# INC-QT1-R-005.net
KiCad netlist of a schematic drawn in Altium Designer
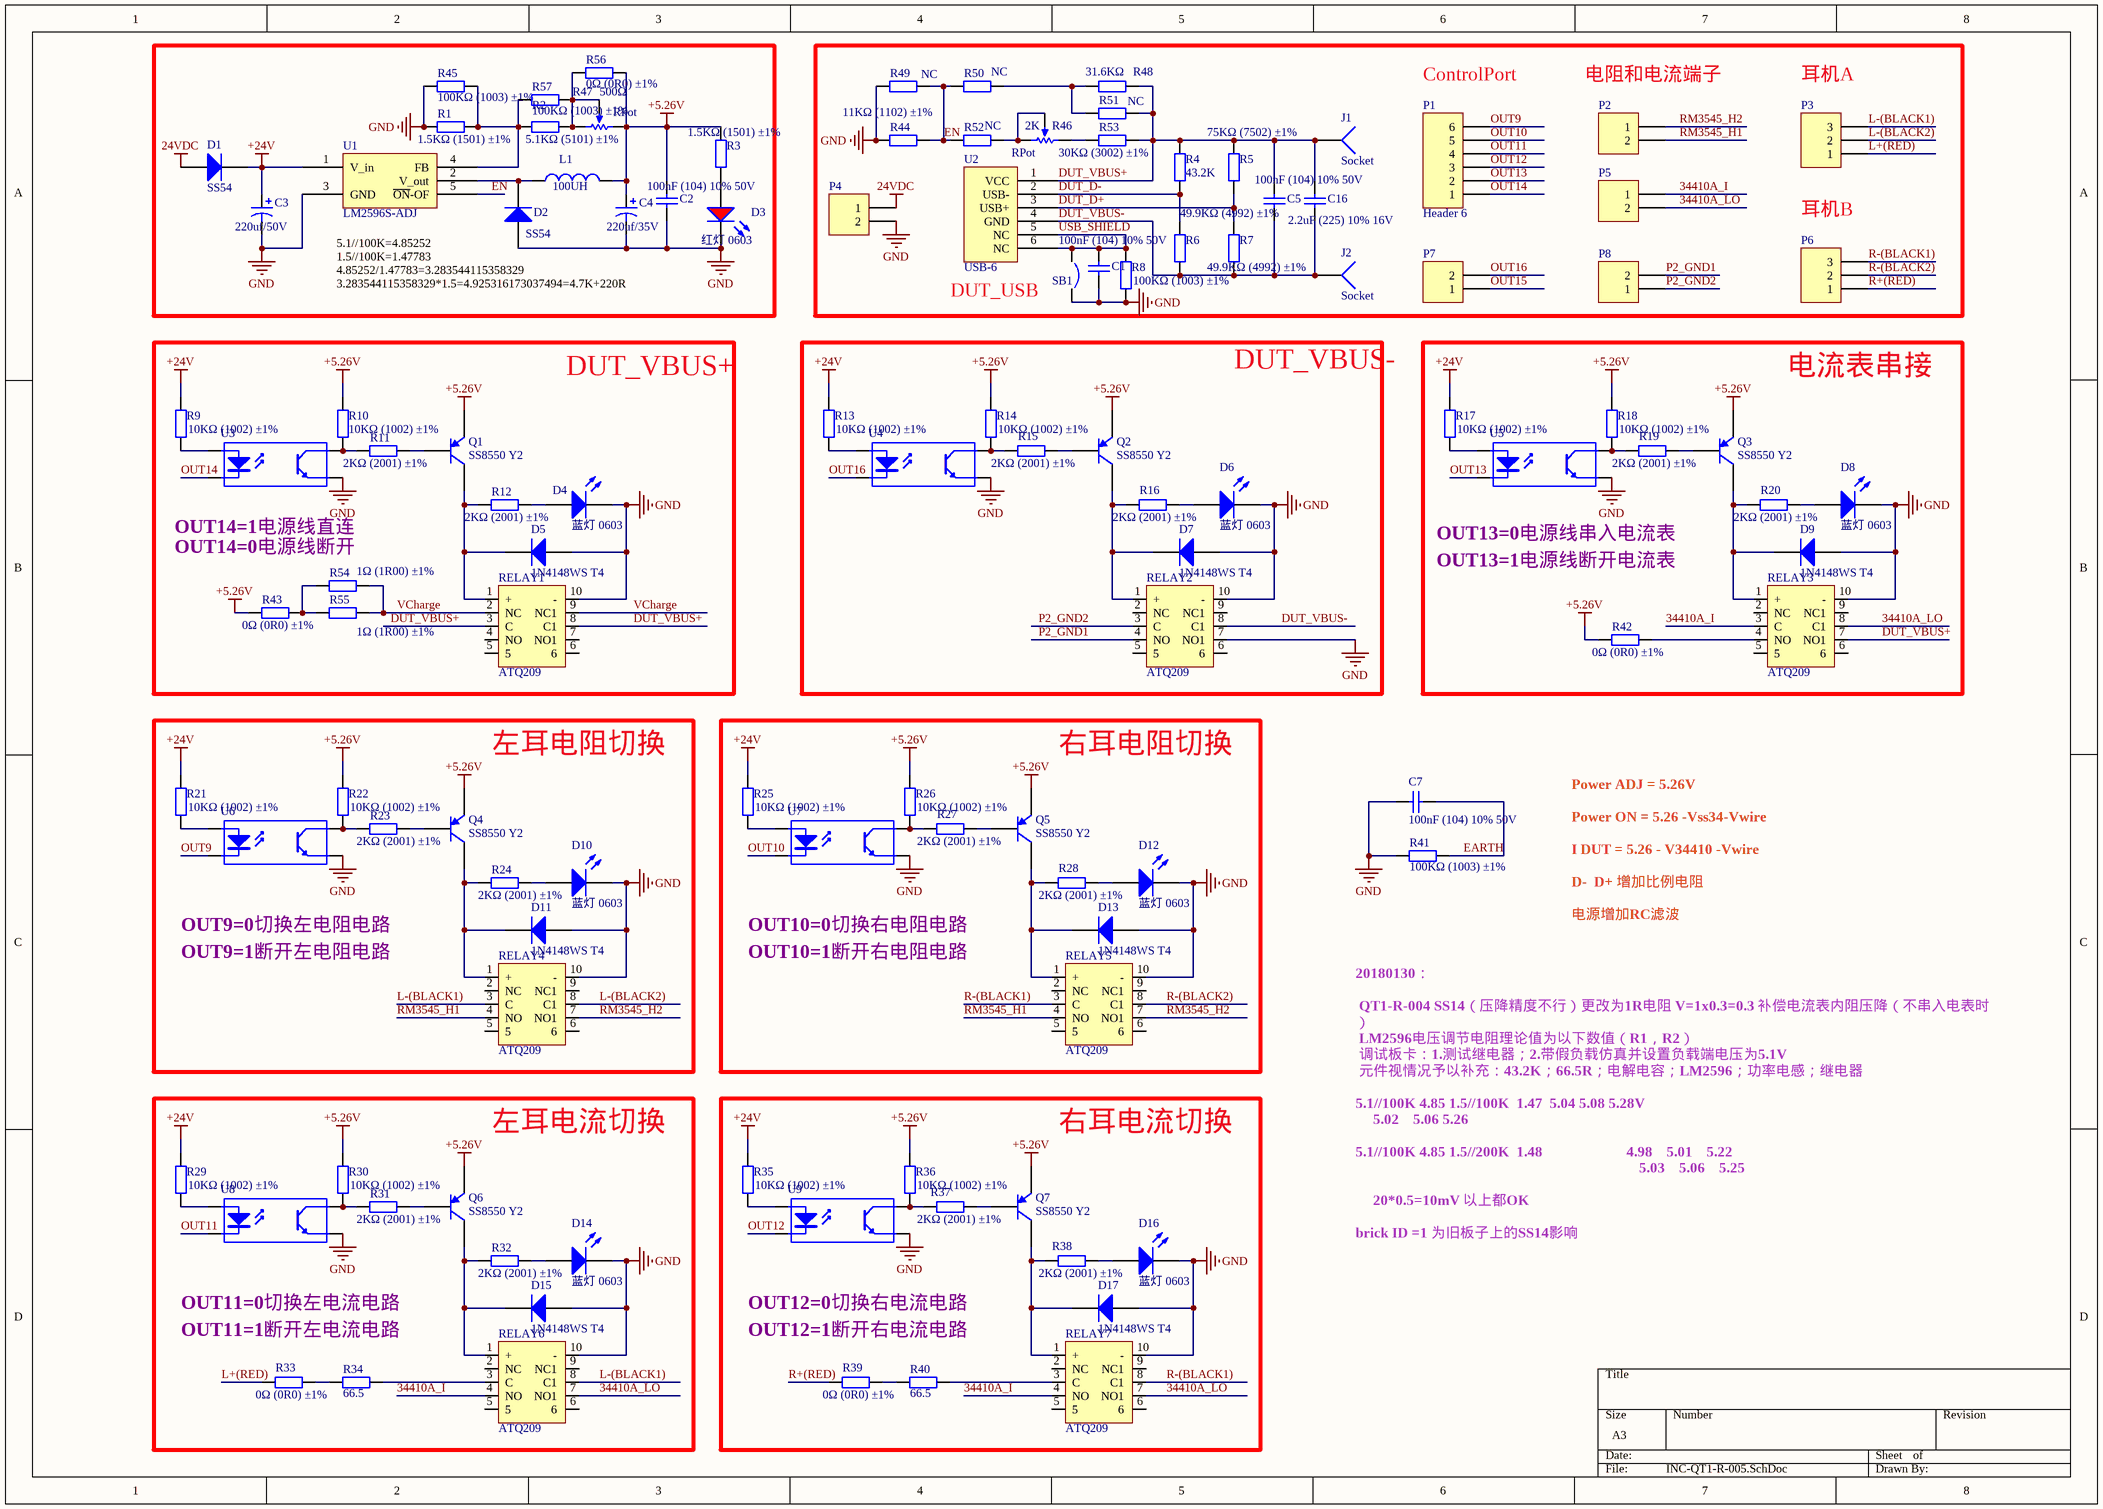
[diagram p0: INC-QT1-R-005.SchDoc]

(export (version "E")
  (design (tool "Eeschema 10.0.6"))
  (components
    (comp (ref "C1")
      (value "100nF (104) 10% 50V")
      (footprint "0603_C")
      (description "贴片电容")
      (libsource (lib "Miscellaneous Devices LC") (part "0603 100nF (104) 10% 50V"))
    )
    (comp (ref "C2")
      (value "100nF (104) 10% 50V")
      (footprint "0603_C")
      (description "贴片电容")
      (libsource (lib "Miscellaneous Devices LC") (part "0603 100nF (104) 10% 50V"))
    )
    (comp (ref "C3")
      (value "220uf/50V")
      (footprint "贴片电解 10mm X 10mm")
      (description "Polarized Capacitor (Radial)")
      (fields (field (name "PUBLISHER") "Altium Limited"))
      (libsource (lib "Miscellaneous Devices") (part "Cap Pol1"))
    )
    (comp (ref "C4")
      (value "220uf/35V")
      (footprint "贴片电解 8mm X 10mm")
      (description "Polarized Capacitor (Radial)")
      (fields (field (name "PUBLISHER") "Altium Limited"))
      (libsource (lib "Miscellaneous Devices") (part "Cap Pol1"))
    )
    (comp (ref "C5")
      (value "100nF (104) 10% 50V")
      (footprint "0603_C")
      (description "贴片电容")
      (libsource (lib "Miscellaneous Devices LC") (part "0603 100nF (104) 10% 50V"))
    )
    (comp (ref "C7")
      (value "100nF (104) 10% 50V")
      (footprint "0603_C")
      (description "贴片电容")
      (libsource (lib "Miscellaneous Devices LC") (part "0603 100nF (104) 10% 50V"))
    )
    (comp (ref "C16")
      (value "2.2uF (225) 10% 16V")
      (footprint "0603_C")
      (description "贴片电容")
      (libsource (lib "Miscellaneous Devices LC") (part "0603 2.2uF (225) 10% 16V"))
    )
    (comp (ref "D1")
      (value "SS54")
      (footprint "SMA(DO-214AC)_S1")
      (description "二极管")
      (libsource (lib "Miscellaneous Devices LC") (part "SMA(DO-214AC) SS54"))
    )
    (comp (ref "D2")
      (value "SS54")
      (footprint "SMA(DO-214AC)_S1")
      (description "二极管")
      (libsource (lib "Miscellaneous Devices LC") (part "SMA(DO-214AC) SS54"))
    )
    (comp (ref "D3")
      (value "红灯 0603")
      (footprint "0603_LED_S1")
      (description "发光二极管")
      (libsource (lib "Miscellaneous Devices LC") (part "0603 红灯"))
    )
    (comp (ref "D4")
      (value "蓝灯 0603")
      (footprint "0603_LED_S1")
      (description "发光二极管")
      (libsource (lib "Miscellaneous Devices LC") (part "0603 蓝灯"))
    )
    (comp (ref "D5")
      (value "1N4148WS T4")
      (footprint "SOD-323")
      (description "二极管")
      (libsource (lib "Miscellaneous Devices LC") (part "SOD-323 1N4148WS T4"))
    )
    (comp (ref "D6")
      (value "蓝灯 0603")
      (footprint "0603_LED_S1")
      (description "发光二极管")
      (libsource (lib "Miscellaneous Devices LC") (part "0603 蓝灯"))
    )
    (comp (ref "D7")
      (value "1N4148WS T4")
      (footprint "SOD-323")
      (description "二极管")
      (libsource (lib "Miscellaneous Devices LC") (part "SOD-323 1N4148WS T4"))
    )
    (comp (ref "D8")
      (value "蓝灯 0603")
      (footprint "0603_LED_S1")
      (description "发光二极管")
      (libsource (lib "Miscellaneous Devices LC") (part "0603 蓝灯"))
    )
    (comp (ref "D9")
      (value "1N4148WS T4")
      (footprint "SOD-323")
      (description "二极管")
      (libsource (lib "Miscellaneous Devices LC") (part "SOD-323 1N4148WS T4"))
    )
    (comp (ref "D10")
      (value "蓝灯 0603")
      (footprint "0603_LED_S1")
      (description "发光二极管")
      (libsource (lib "Miscellaneous Devices LC") (part "0603 蓝灯"))
    )
    (comp (ref "D11")
      (value "1N4148WS T4")
      (footprint "SOD-323")
      (description "二极管")
      (libsource (lib "Miscellaneous Devices LC") (part "SOD-323 1N4148WS T4"))
    )
    (comp (ref "D12")
      (value "蓝灯 0603")
      (footprint "0603_LED_S1")
      (description "发光二极管")
      (libsource (lib "Miscellaneous Devices LC") (part "0603 蓝灯"))
    )
    (comp (ref "D13")
      (value "1N4148WS T4")
      (footprint "SOD-323")
      (description "二极管")
      (libsource (lib "Miscellaneous Devices LC") (part "SOD-323 1N4148WS T4"))
    )
    (comp (ref "D14")
      (value "蓝灯 0603")
      (footprint "0603_LED_S1")
      (description "发光二极管")
      (libsource (lib "Miscellaneous Devices LC") (part "0603 蓝灯"))
    )
    (comp (ref "D15")
      (value "1N4148WS T4")
      (footprint "SOD-323")
      (description "二极管")
      (libsource (lib "Miscellaneous Devices LC") (part "SOD-323 1N4148WS T4"))
    )
    (comp (ref "D16")
      (value "蓝灯 0603")
      (footprint "0603_LED_S1")
      (description "发光二极管")
      (libsource (lib "Miscellaneous Devices LC") (part "0603 蓝灯"))
    )
    (comp (ref "D17")
      (value "1N4148WS T4")
      (footprint "SOD-323")
      (description "二极管")
      (libsource (lib "Miscellaneous Devices LC") (part "SOD-323 1N4148WS T4"))
    )
    (comp (ref "J1")
      (value "Socket")
      (footprint "TP")
      (fields (field (name "PUBLISHER") "Altium Limited"))
      (libsource (lib "Miscellaneous Connectors") (part "Socket"))
    )
    (comp (ref "J2")
      (value "Socket")
      (footprint "TP")
      (fields (field (name "PUBLISHER") "Altium Limited"))
      (libsource (lib "Miscellaneous Connectors") (part "Socket"))
    )
    (comp (ref "L1")
      (value "100UH")
      (footprint "贴片电感 12*12")
      (description "Inductor")
      (fields (field (name "PUBLISHER") "Altium Limited"))
      (libsource (lib "Miscellaneous Devices") (part "Inductor"))
    )
    (comp (ref "P1")
      (value "Header 6")
      (footprint "WJ15EDGVC-3.81-6P")
      (description "Header, 6-Pin")
      (fields (field (name "PUBLISHER") "Altium Limited"))
      (libsource (lib "Miscellaneous Connectors") (part "Header 6"))
    )
    (comp (ref "P2")
      (value "Header 2")
      (footprint "WJ15EDGVC-3.81-2P")
      (description "Header, 2-Pin")
      (fields (field (name "PUBLISHER") "Altium Limited"))
      (libsource (lib "Miscellaneous Connectors") (part "Header 2"))
    )
    (comp (ref "P3")
      (value "Header 3")
      (footprint "WJ15EDGVC-3.81-3P")
      (description "Header, 3-Pin")
      (fields (field (name "PUBLISHER") "Altium Limited"))
      (libsource (lib "Miscellaneous Connectors") (part "Header 3"))
    )
    (comp (ref "P4")
      (value "Header 2")
      (footprint "WJ15EDGVC-3.81-2P")
      (description "Header, 2-Pin")
      (fields (field (name "PUBLISHER") "Altium Limited"))
      (libsource (lib "Miscellaneous Connectors") (part "Header 2"))
    )
    (comp (ref "P5")
      (value "Header 2")
      (footprint "WJ15EDGVC-3.81-2P")
      (description "Header, 2-Pin")
      (fields (field (name "PUBLISHER") "Altium Limited"))
      (libsource (lib "Miscellaneous Connectors") (part "Header 2"))
    )
    (comp (ref "P6")
      (value "Header 3")
      (footprint "WJ15EDGVC-3.81-3P")
      (description "Header, 3-Pin")
      (fields (field (name "PUBLISHER") "Altium Limited"))
      (libsource (lib "Miscellaneous Connectors") (part "Header 3"))
    )
    (comp (ref "P7")
      (value "Header 2")
      (footprint "WJ15EDGVC-3.81-2P")
      (description "Header, 2-Pin")
      (fields (field (name "PUBLISHER") "Altium Limited"))
      (libsource (lib "") (part "Header 2_1"))
    )
    (comp (ref "P8")
      (value "Header 2")
      (footprint "WJ15EDGVC-3.81-2P")
      (description "Header, 2-Pin")
      (fields (field (name "PUBLISHER") "Altium Limited"))
      (libsource (lib "") (part "Header 2_1"))
    )
    (comp (ref "Q1")
      (value "SS8550 Y2")
      (footprint "SOT-23(SOT-23-3)")
      (description "三极管")
      (libsource (lib "Miscellaneous Devices LC") (part "SOT-23 SS8550 Y2"))
    )
    (comp (ref "Q2")
      (value "SS8550 Y2")
      (footprint "SOT-23(SOT-23-3)")
      (description "三极管")
      (libsource (lib "Miscellaneous Devices LC") (part "SOT-23 SS8550 Y2"))
    )
    (comp (ref "Q3")
      (value "SS8550 Y2")
      (footprint "SOT-23(SOT-23-3)")
      (description "三极管")
      (libsource (lib "Miscellaneous Devices LC") (part "SOT-23 SS8550 Y2"))
    )
    (comp (ref "Q4")
      (value "SS8550 Y2")
      (footprint "SOT-23(SOT-23-3)")
      (description "三极管")
      (libsource (lib "Miscellaneous Devices LC") (part "SOT-23 SS8550 Y2"))
    )
    (comp (ref "Q5")
      (value "SS8550 Y2")
      (footprint "SOT-23(SOT-23-3)")
      (description "三极管")
      (libsource (lib "Miscellaneous Devices LC") (part "SOT-23 SS8550 Y2"))
    )
    (comp (ref "Q6")
      (value "SS8550 Y2")
      (footprint "SOT-23(SOT-23-3)")
      (description "三极管")
      (libsource (lib "Miscellaneous Devices LC") (part "SOT-23 SS8550 Y2"))
    )
    (comp (ref "Q7")
      (value "SS8550 Y2")
      (footprint "SOT-23(SOT-23-3)")
      (description "三极管")
      (libsource (lib "Miscellaneous Devices LC") (part "SOT-23 SS8550 Y2"))
    )
    (comp (ref "R1")
      (value "1.5KΩ (1501) ±1%")
      (footprint "0603_R")
      (description "贴片电阻")
      (libsource (lib "Miscellaneous Devices LC") (part "0603 1.5KΩ (1501) 1%"))
    )
    (comp (ref "R2")
      (value "5.1KΩ (5101) ±1%")
      (footprint "0603_R")
      (description "贴片电阻")
      (libsource (lib "Miscellaneous Devices LC") (part "0603 5.1KΩ (5101) 1%"))
    )
    (comp (ref "R3")
      (value "1.5KΩ (1501) ±1%")
      (footprint "0603_R")
      (description "贴片电阻")
      (libsource (lib "") (part "0603 1.5KΩ (1501) 1%_1"))
    )
    (comp (ref "R4")
      (value "43.2K")
      (footprint "0603_R")
      (description "Resistor")
      (fields (field (name "PUBLISHER") "Altium Limited"))
      (libsource (lib "") (part "Res2_1"))
    )
    (comp (ref "R5")
      (value "75KΩ (7502) ±1%")
      (footprint "0603_R")
      (description "贴片电阻")
      (libsource (lib "Miscellaneous Devices LC") (part "0603 75KΩ (7502) 1%"))
    )
    (comp (ref "R6")
      (value "49.9KΩ (4992) ±1%")
      (footprint "0603_R")
      (description "贴片电阻")
      (libsource (lib "Miscellaneous Devices LC") (part "0603 49.9KΩ (4992) 1%"))
    )
    (comp (ref "R7")
      (value "49.9KΩ (4992) ±1%")
      (footprint "0603_R")
      (description "贴片电阻")
      (libsource (lib "Miscellaneous Devices LC") (part "0603 49.9KΩ (4992) 1%"))
    )
    (comp (ref "R8")
      (value "100KΩ (1003) ±1%")
      (footprint "0603_R")
      (description "贴片电阻")
      (libsource (lib "") (part "0603 100KΩ (1003) 1%_2"))
    )
    (comp (ref "R9")
      (value "10KΩ (1002) ±1%")
      (footprint "0603_R")
      (description "贴片电阻")
      (libsource (lib "Miscellaneous Devices LC") (part "0603 10KΩ (1002) 1%"))
    )
    (comp (ref "R10")
      (value "10KΩ (1002) ±1%")
      (footprint "0603_R")
      (description "贴片电阻")
      (libsource (lib "Miscellaneous Devices LC") (part "0603 10KΩ (1002) 1%"))
    )
    (comp (ref "R11")
      (value "2KΩ (2001) ±1%")
      (footprint "0603_R")
      (description "贴片电阻")
      (libsource (lib "Miscellaneous Devices LC") (part "0603 2KΩ (2001) 1%"))
    )
    (comp (ref "R12")
      (value "2KΩ (2001) ±1%")
      (footprint "0603_R")
      (description "贴片电阻")
      (libsource (lib "Miscellaneous Devices LC") (part "0603 2KΩ (2001) 1%"))
    )
    (comp (ref "R13")
      (value "10KΩ (1002) ±1%")
      (footprint "0603_R")
      (description "贴片电阻")
      (libsource (lib "Miscellaneous Devices LC") (part "0603 10KΩ (1002) 1%"))
    )
    (comp (ref "R14")
      (value "10KΩ (1002) ±1%")
      (footprint "0603_R")
      (description "贴片电阻")
      (libsource (lib "Miscellaneous Devices LC") (part "0603 10KΩ (1002) 1%"))
    )
    (comp (ref "R15")
      (value "2KΩ (2001) ±1%")
      (footprint "0603_R")
      (description "贴片电阻")
      (libsource (lib "Miscellaneous Devices LC") (part "0603 2KΩ (2001) 1%"))
    )
    (comp (ref "R16")
      (value "2KΩ (2001) ±1%")
      (footprint "0603_R")
      (description "贴片电阻")
      (libsource (lib "Miscellaneous Devices LC") (part "0603 2KΩ (2001) 1%"))
    )
    (comp (ref "R17")
      (value "10KΩ (1002) ±1%")
      (footprint "0603_R")
      (description "贴片电阻")
      (libsource (lib "Miscellaneous Devices LC") (part "0603 10KΩ (1002) 1%"))
    )
    (comp (ref "R18")
      (value "10KΩ (1002) ±1%")
      (footprint "0603_R")
      (description "贴片电阻")
      (libsource (lib "Miscellaneous Devices LC") (part "0603 10KΩ (1002) 1%"))
    )
    (comp (ref "R19")
      (value "2KΩ (2001) ±1%")
      (footprint "0603_R")
      (description "贴片电阻")
      (libsource (lib "Miscellaneous Devices LC") (part "0603 2KΩ (2001) 1%"))
    )
    (comp (ref "R20")
      (value "2KΩ (2001) ±1%")
      (footprint "0603_R")
      (description "贴片电阻")
      (libsource (lib "Miscellaneous Devices LC") (part "0603 2KΩ (2001) 1%"))
    )
    (comp (ref "R21")
      (value "10KΩ (1002) ±1%")
      (footprint "0603_R")
      (description "贴片电阻")
      (libsource (lib "Miscellaneous Devices LC") (part "0603 10KΩ (1002) 1%"))
    )
    (comp (ref "R22")
      (value "10KΩ (1002) ±1%")
      (footprint "0603_R")
      (description "贴片电阻")
      (libsource (lib "Miscellaneous Devices LC") (part "0603 10KΩ (1002) 1%"))
    )
    (comp (ref "R23")
      (value "2KΩ (2001) ±1%")
      (footprint "0603_R")
      (description "贴片电阻")
      (libsource (lib "Miscellaneous Devices LC") (part "0603 2KΩ (2001) 1%"))
    )
    (comp (ref "R24")
      (value "2KΩ (2001) ±1%")
      (footprint "0603_R")
      (description "贴片电阻")
      (libsource (lib "Miscellaneous Devices LC") (part "0603 2KΩ (2001) 1%"))
    )
    (comp (ref "R25")
      (value "10KΩ (1002) ±1%")
      (footprint "0603_R")
      (description "贴片电阻")
      (libsource (lib "Miscellaneous Devices LC") (part "0603 10KΩ (1002) 1%"))
    )
    (comp (ref "R26")
      (value "10KΩ (1002) ±1%")
      (footprint "0603_R")
      (description "贴片电阻")
      (libsource (lib "Miscellaneous Devices LC") (part "0603 10KΩ (1002) 1%"))
    )
    (comp (ref "R27")
      (value "2KΩ (2001) ±1%")
      (footprint "0603_R")
      (description "贴片电阻")
      (libsource (lib "Miscellaneous Devices LC") (part "0603 2KΩ (2001) 1%"))
    )
    (comp (ref "R28")
      (value "2KΩ (2001) ±1%")
      (footprint "0603_R")
      (description "贴片电阻")
      (libsource (lib "Miscellaneous Devices LC") (part "0603 2KΩ (2001) 1%"))
    )
    (comp (ref "R29")
      (value "10KΩ (1002) ±1%")
      (footprint "0603_R")
      (description "贴片电阻")
      (libsource (lib "Miscellaneous Devices LC") (part "0603 10KΩ (1002) 1%"))
    )
    (comp (ref "R30")
      (value "10KΩ (1002) ±1%")
      (footprint "0603_R")
      (description "贴片电阻")
      (libsource (lib "Miscellaneous Devices LC") (part "0603 10KΩ (1002) 1%"))
    )
    (comp (ref "R31")
      (value "2KΩ (2001) ±1%")
      (footprint "0603_R")
      (description "贴片电阻")
      (libsource (lib "Miscellaneous Devices LC") (part "0603 2KΩ (2001) 1%"))
    )
    (comp (ref "R32")
      (value "2KΩ (2001) ±1%")
      (footprint "0603_R")
      (description "贴片电阻")
      (libsource (lib "Miscellaneous Devices LC") (part "0603 2KΩ (2001) 1%"))
    )
    (comp (ref "R33")
      (value "0Ω (0R0) ±1%")
      (footprint "0805_R")
      (description "贴片电阻")
      (libsource (lib "Miscellaneous Devices LC") (part "0805 0Ω (0R0) 1%"))
    )
    (comp (ref "R34")
      (value "66.5")
      (footprint "2512_R")
      (description "Resistor")
      (fields (field (name "PUBLISHER") "Altium Limited"))
      (libsource (lib "Miscellaneous Devices") (part "Res2"))
    )
    (comp (ref "R35")
      (value "10KΩ (1002) ±1%")
      (footprint "0603_R")
      (description "贴片电阻")
      (libsource (lib "Miscellaneous Devices LC") (part "0603 10KΩ (1002) 1%"))
    )
    (comp (ref "R36")
      (value "10KΩ (1002) ±1%")
      (footprint "0603_R")
      (description "贴片电阻")
      (libsource (lib "Miscellaneous Devices LC") (part "0603 10KΩ (1002) 1%"))
    )
    (comp (ref "R37")
      (value "2KΩ (2001) ±1%")
      (footprint "0603_R")
      (description "贴片电阻")
      (libsource (lib "Miscellaneous Devices LC") (part "0603 2KΩ (2001) 1%"))
    )
    (comp (ref "R38")
      (value "2KΩ (2001) ±1%")
      (footprint "0603_R")
      (description "贴片电阻")
      (libsource (lib "Miscellaneous Devices LC") (part "0603 2KΩ (2001) 1%"))
    )
    (comp (ref "R39")
      (value "0Ω (0R0) ±1%")
      (footprint "0805_R")
      (description "贴片电阻")
      (libsource (lib "Miscellaneous Devices LC") (part "0805 0Ω (0R0) 1%"))
    )
    (comp (ref "R40")
      (value "66.5")
      (footprint "2512_R")
      (description "Resistor")
      (fields (field (name "PUBLISHER") "Altium Limited"))
      (libsource (lib "Miscellaneous Devices") (part "Res2"))
    )
    (comp (ref "R41")
      (value "100KΩ (1003) ±1%")
      (footprint "0603_R")
      (description "贴片电阻")
      (libsource (lib "Miscellaneous Devices LC") (part "0603 100KΩ (1003) 1%"))
    )
    (comp (ref "R42")
      (value "0Ω (0R0) ±1%")
      (footprint "0805_R")
      (description "贴片电阻")
      (libsource (lib "Miscellaneous Devices LC") (part "0805 0Ω (0R0) 1%"))
    )
    (comp (ref "R43")
      (value "0Ω (0R0) ±1%")
      (footprint "0805_R")
      (description "贴片电阻")
      (libsource (lib "Miscellaneous Devices LC") (part "0805 0Ω (0R0) 1%"))
    )
    (comp (ref "R44")
      (value "11KΩ (1102) ±1%")
      (footprint "0603_R")
      (description "贴片电阻")
      (libsource (lib "Miscellaneous Devices LC") (part "0603 11KΩ (1102) 1%"))
    )
    (comp (ref "R45")
      (value "100KΩ (1003) ±1%")
      (footprint "0603_R")
      (description "贴片电阻")
      (libsource (lib "") (part "0603 100KΩ (1003) 1%_1"))
    )
    (comp (ref "R46")
      (value "RPot")
      (footprint "插件可调电阻 3362P")
      (description "Potentiometer")
      (fields (field (name "ALTIUM_VALUE") "2K") (field (name "PUBLISHER") "Altium Limited"))
      (libsource (lib "Miscellaneous Devices") (part "RPot"))
    )
    (comp (ref "R47")
      (value "RPot")
      (footprint "插件可调电阻 3362P")
      (description "Potentiometer")
      (fields (field (name "ALTIUM_VALUE") "500Ω") (field (name "PUBLISHER") "Altium Limited"))
      (libsource (lib "Miscellaneous Devices") (part "RPot"))
    )
    (comp (ref "R48")
      (value "31.6KΩ")
      (footprint "0603_R")
      (description "贴片电阻")
      (libsource (lib "Miscellaneous Devices LC") (part "0603 510KΩ (5103) 1%"))
    )
    (comp (ref "R49")
      (value "NC")
      (footprint "0603_R")
      (description "贴片电阻")
      (libsource (lib "Miscellaneous Devices LC") (part "0603 510KΩ (5103) 1%"))
    )
    (comp (ref "R50")
      (value "NC")
      (footprint "0603_R")
      (description "贴片电阻")
      (libsource (lib "Miscellaneous Devices LC") (part "0603 0Ω (0R0) 1%"))
    )
    (comp (ref "R51")
      (value "NC")
      (footprint "0603_R")
      (description "贴片电阻")
      (libsource (lib "Miscellaneous Devices LC") (part "0603 510KΩ (5103) 1%"))
    )
    (comp (ref "R52")
      (value "NC")
      (footprint "0603_R")
      (description "贴片电阻")
      (libsource (lib "Miscellaneous Devices LC") (part "0603 0Ω (0R0) 1%"))
    )
    (comp (ref "R53")
      (value "30KΩ (3002) ±1%")
      (footprint "0603_R")
      (description "贴片电阻")
      (libsource (lib "Miscellaneous Devices LC") (part "0603 30KΩ (3002) 1%"))
    )
    (comp (ref "R54")
      (value "1Ω (1R00) ±1%")
      (footprint "1206_R")
      (description "贴片电阻")
      (libsource (lib "") (part "1206 1Ω (1R00) 1%_1"))
    )
    (comp (ref "R55")
      (value "1Ω (1R00) ±1%")
      (footprint "1206_R")
      (description "贴片电阻")
      (libsource (lib "Miscellaneous Devices LC") (part "1206 1Ω (1R00) 1%"))
    )
    (comp (ref "R56")
      (value "0Ω (0R0) ±1%")
      (footprint "0603_R")
      (description "贴片电阻")
      (libsource (lib "Miscellaneous Devices LC") (part "0603 0Ω (0R0) 1%"))
    )
    (comp (ref "R57")
      (value "100KΩ (1003) ±1%")
      (footprint "0603_R")
      (description "贴片电阻")
      (libsource (lib "") (part "0603 100KΩ (1003) 1%_1"))
    )
    (comp (ref "RELAY1") (value "ATQ209") (footprint "插件继电器 TQ2-5V") (libsource (lib "*") (part "ATQ209")))
    (comp (ref "RELAY2") (value "ATQ209") (footprint "插件继电器 TQ2-5V") (libsource (lib "*") (part "ATQ209")))
    (comp (ref "RELAY3") (value "ATQ209") (footprint "插件继电器 TQ2-5V") (libsource (lib "*") (part "ATQ209")))
    (comp (ref "RELAY4") (value "ATQ209") (footprint "插件继电器 TQ2-5V") (libsource (lib "*") (part "ATQ209")))
    (comp (ref "RELAY5") (value "ATQ209") (footprint "插件继电器 TQ2-5V") (libsource (lib "*") (part "ATQ209")))
    (comp (ref "RELAY6") (value "ATQ209") (footprint "插件继电器 TQ2-5V") (libsource (lib "*") (part "ATQ209")))
    (comp (ref "RELAY7") (value "ATQ209") (footprint "插件继电器 TQ2-5V") (libsource (lib "*") (part "ATQ209")))
    (comp (ref "SB1")
      (value "Circuit Breaker")
      (footprint "JP2_SMD")
      (fields (field (name "PUBLISHER") "Altium Limited"))
      (libsource (lib "MCD_TOOLS") (part "Circuit Breaker"))
    )
    (comp (ref "U1")
      (value "LM2596S-ADJ")
      (footprint "LM2596-ADJ-263-5")
      (libsource (lib "GB-SCH") (part "LM2596-ADJ"))
    )
    (comp (ref "U2") (value "USB-6") (footprint "USB_TypeA") (libsource (lib "GB-SCH") (part "USB-6")))
    (comp (ref "U3")
      (value "EL357N(B)(TA)-G")
      (footprint "SOP-4_P2.54")
      (description "4-Pin Phototransistor Optocoupler")
      (fields (field (name "PUBLISHER") "Altium Limited"))
      (libsource (lib "Miscellaneous Devices") (part "Optoisolator1"))
    )
    (comp (ref "U4")
      (value "EL357N(B)(TA)-G")
      (footprint "SOP-4_P2.54")
      (description "4-Pin Phototransistor Optocoupler")
      (fields (field (name "PUBLISHER") "Altium Limited"))
      (libsource (lib "Miscellaneous Devices") (part "Optoisolator1"))
    )
    (comp (ref "U5")
      (value "EL357N(B)(TA)-G")
      (footprint "SOP-4_P2.54")
      (description "4-Pin Phototransistor Optocoupler")
      (fields (field (name "PUBLISHER") "Altium Limited"))
      (libsource (lib "Miscellaneous Devices") (part "Optoisolator1"))
    )
    (comp (ref "U6")
      (value "EL357N(B)(TA)-G")
      (footprint "SOP-4_P2.54")
      (description "4-Pin Phototransistor Optocoupler")
      (fields (field (name "PUBLISHER") "Altium Limited"))
      (libsource (lib "Miscellaneous Devices") (part "Optoisolator1"))
    )
    (comp (ref "U7")
      (value "EL357N(B)(TA)-G")
      (footprint "SOP-4_P2.54")
      (description "4-Pin Phototransistor Optocoupler")
      (fields (field (name "PUBLISHER") "Altium Limited"))
      (libsource (lib "Miscellaneous Devices") (part "Optoisolator1"))
    )
    (comp (ref "U8")
      (value "EL357N(B)(TA)-G")
      (footprint "SOP-4_P2.54")
      (description "4-Pin Phototransistor Optocoupler")
      (fields (field (name "PUBLISHER") "Altium Limited"))
      (libsource (lib "Miscellaneous Devices") (part "Optoisolator1"))
    )
    (comp (ref "U9")
      (value "EL357N(B)(TA)-G")
      (footprint "SOP-4_P2.54")
      (description "4-Pin Phototransistor Optocoupler")
      (fields (field (name "PUBLISHER") "Altium Limited"))
      (libsource (lib "Miscellaneous Devices") (part "Optoisolator1"))
    )
  )
  (nets
    (net (code "1") (name "+5.26V") (class "Default")
      (node (ref "C2") (pin "2") (pinfunction "2_2") (pintype "passive"))
      (node (ref "C4") (pin "1") (pinfunction "1_1") (pintype "passive"))
      (node (ref "L1") (pin "2") (pinfunction "2_2") (pintype "passive"))
      (node (ref "Q1") (pin "2") (pinfunction "E_2") (pintype "passive"))
      (node (ref "Q2") (pin "2") (pinfunction "E_2") (pintype "passive"))
      (node (ref "Q3") (pin "2") (pinfunction "E_2") (pintype "passive"))
      (node (ref "Q4") (pin "2") (pinfunction "E_2") (pintype "passive"))
      (node (ref "Q5") (pin "2") (pinfunction "E_2") (pintype "passive"))
      (node (ref "Q6") (pin "2") (pinfunction "E_2") (pintype "passive"))
      (node (ref "Q7") (pin "2") (pinfunction "E_2") (pintype "passive"))
      (node (ref "R10") (pin "2") (pinfunction "2_2") (pintype "passive"))
      (node (ref "R14") (pin "2") (pinfunction "2_2") (pintype "passive"))
      (node (ref "R18") (pin "2") (pinfunction "2_2") (pintype "passive"))
      (node (ref "R22") (pin "2") (pinfunction "2_2") (pintype "passive"))
      (node (ref "R26") (pin "2") (pinfunction "2_2") (pintype "passive"))
      (node (ref "R3") (pin "2") (pinfunction "2_2") (pintype "passive"))
      (node (ref "R30") (pin "2") (pinfunction "2_2") (pintype "passive"))
      (node (ref "R36") (pin "2") (pinfunction "2_2") (pintype "passive"))
      (node (ref "R42") (pin "1") (pinfunction "1_1") (pintype "passive"))
      (node (ref "R43") (pin "1") (pinfunction "1_1") (pintype "passive"))
      (node (ref "R47") (pin "1") (pinfunction "TOP_1") (pintype "passive"))
      (node (ref "R56") (pin "2") (pinfunction "2_2") (pintype "passive"))
    )
    (net (code "2") (name "+24V") (class "Default")
      (node (ref "C3") (pin "1") (pinfunction "1_1") (pintype "passive"))
      (node (ref "D1") (pin "2") (pinfunction "K_2") (pintype "passive"))
      (node (ref "R13") (pin "2") (pinfunction "2_2") (pintype "passive"))
      (node (ref "R17") (pin "2") (pinfunction "2_2") (pintype "passive"))
      (node (ref "R21") (pin "2") (pinfunction "2_2") (pintype "passive"))
      (node (ref "R25") (pin "2") (pinfunction "2_2") (pintype "passive"))
      (node (ref "R29") (pin "2") (pinfunction "2_2") (pintype "passive"))
      (node (ref "R35") (pin "2") (pinfunction "2_2") (pintype "passive"))
      (node (ref "R9") (pin "2") (pinfunction "2_2") (pintype "passive"))
      (node (ref "U1") (pin "1") (pinfunction "V_in_1") (pintype "passive"))
    )
    (net (code "3") (name "/34410A_I") (class "Default")
      (node (ref "P5") (pin "1") (pinfunction "1_1") (pintype "passive"))
      (node (ref "RELAY3") (pin "3") (pinfunction "C_3") (pintype "passive"))
      (node (ref "RELAY6") (pin "4") (pinfunction "NO_4") (pintype "passive"))
      (node (ref "RELAY7") (pin "4") (pinfunction "NO_4") (pintype "passive"))
    )
    (net (code "4") (name "/34410A_LO") (class "Default")
      (node (ref "P5") (pin "2") (pinfunction "2_2") (pintype "passive"))
      (node (ref "RELAY3") (pin "8") (pinfunction "C1_8") (pintype "passive"))
      (node (ref "RELAY6") (pin "7") (pinfunction "NO1_7") (pintype "passive"))
      (node (ref "RELAY7") (pin "7") (pinfunction "NO1_7") (pintype "passive"))
    )
    (net (code "5") (name "/DUT_D+") (class "Default")
      (node (ref "R5") (pin "1") (pinfunction "1_1") (pintype "passive"))
      (node (ref "R7") (pin "2") (pinfunction "2_2") (pintype "passive"))
      (node (ref "U2") (pin "3") (pinfunction "USB+_3") (pintype "passive"))
    )
    (net (code "6") (name "/DUT_D-") (class "Default")
      (node (ref "R4") (pin "1") (pinfunction "1_1") (pintype "passive"))
      (node (ref "R6") (pin "2") (pinfunction "2_2") (pintype "passive"))
      (node (ref "U2") (pin "2") (pinfunction "USB-_2") (pintype "passive"))
    )
    (net (code "7") (name "/DUT_VBUS+") (class "Default")
      (node (ref "C16") (pin "2") (pinfunction "2_2") (pintype "passive"))
      (node (ref "C5") (pin "2") (pinfunction "2_2") (pintype "passive"))
      (node (ref "J1") (pin "1") (pinfunction "1_1") (pintype "passive"))
      (node (ref "R4") (pin "2") (pinfunction "2_2") (pintype "passive"))
      (node (ref "R48") (pin "2") (pinfunction "2_2") (pintype "passive"))
      (node (ref "R5") (pin "2") (pinfunction "2_2") (pintype "passive"))
      (node (ref "R51") (pin "2") (pinfunction "2_2") (pintype "passive"))
      (node (ref "R53") (pin "2") (pinfunction "2_2") (pintype "passive"))
      (node (ref "RELAY1") (pin "3") (pinfunction "C_3") (pintype "passive"))
      (node (ref "RELAY1") (pin "8") (pinfunction "C1_8") (pintype "passive"))
      (node (ref "RELAY3") (pin "7") (pinfunction "NO1_7") (pintype "passive"))
      (node (ref "U2") (pin "1") (pinfunction "VCC_1") (pintype "passive"))
    )
    (net (code "8") (name "/DUT_VBUS-") (class "Default")
      (node (ref "C16") (pin "1") (pinfunction "1_1") (pintype "passive"))
      (node (ref "C5") (pin "1") (pinfunction "1_1") (pintype "passive"))
      (node (ref "J2") (pin "1") (pinfunction "1_1") (pintype "passive"))
      (node (ref "R6") (pin "1") (pinfunction "1_1") (pintype "passive"))
      (node (ref "R7") (pin "1") (pinfunction "1_1") (pintype "passive"))
      (node (ref "RELAY2") (pin "8") (pinfunction "C1_8") (pintype "passive"))
      (node (ref "U2") (pin "4") (pinfunction "GND_4") (pintype "passive"))
    )
    (net (code "9") (name "/EARTH") (class "Default")
      (node (ref "C7") (pin "1") (pinfunction "1_1") (pintype "passive"))
      (node (ref "R41") (pin "1") (pinfunction "1_1") (pintype "passive"))
    )
    (net (code "10") (name "/EN") (class "Default")
      (node (ref "R44") (pin "2") (pinfunction "2_2") (pintype "passive"))
      (node (ref "R49") (pin "2") (pinfunction "2_2") (pintype "passive"))
      (node (ref "R50") (pin "1") (pinfunction "1_1") (pintype "passive"))
      (node (ref "R52") (pin "1") (pinfunction "1_1") (pintype "passive"))
      (node (ref "U1") (pin "5") (pinfunction "~{ON}-OF_5") (pintype "passive"))
    )
    (net (code "11") (name "/L+(RED)") (class "Default")
      (node (ref "P3") (pin "1") (pinfunction "1_1") (pintype "passive"))
      (node (ref "R33") (pin "1") (pinfunction "1_1") (pintype "passive"))
    )
    (net (code "12") (name "/L-(BLACK1)") (class "Default")
      (node (ref "P3") (pin "3") (pinfunction "3_3") (pintype "passive"))
      (node (ref "RELAY4") (pin "3") (pinfunction "C_3") (pintype "passive"))
      (node (ref "RELAY6") (pin "8") (pinfunction "C1_8") (pintype "passive"))
    )
    (net (code "13") (name "/L-(BLACK2)") (class "Default")
      (node (ref "P3") (pin "2") (pinfunction "2_2") (pintype "passive"))
      (node (ref "RELAY4") (pin "8") (pinfunction "C1_8") (pintype "passive"))
    )
    (net (code "14") (name "/OUT9") (class "Default")
      (node (ref "P1") (pin "6") (pinfunction "6_6") (pintype "passive"))
      (node (ref "U6") (pin "2") (pinfunction "K_2") (pintype "passive"))
    )
    (net (code "15") (name "/OUT10") (class "Default")
      (node (ref "P1") (pin "5") (pinfunction "5_5") (pintype "passive"))
      (node (ref "U7") (pin "2") (pinfunction "K_2") (pintype "passive"))
    )
    (net (code "16") (name "/OUT11") (class "Default")
      (node (ref "P1") (pin "4") (pinfunction "4_4") (pintype "passive"))
      (node (ref "U8") (pin "2") (pinfunction "K_2") (pintype "passive"))
    )
    (net (code "17") (name "/OUT12") (class "Default")
      (node (ref "P1") (pin "3") (pinfunction "3_3") (pintype "passive"))
      (node (ref "U9") (pin "2") (pinfunction "K_2") (pintype "passive"))
    )
    (net (code "18") (name "/OUT13") (class "Default")
      (node (ref "P1") (pin "2") (pinfunction "2_2") (pintype "passive"))
      (node (ref "U5") (pin "2") (pinfunction "K_2") (pintype "passive"))
    )
    (net (code "19") (name "/OUT14") (class "Default")
      (node (ref "P1") (pin "1") (pinfunction "1_1") (pintype "passive"))
      (node (ref "U3") (pin "2") (pinfunction "K_2") (pintype "passive"))
    )
    (net (code "20") (name "/OUT15") (class "Default")
      (node (ref "P7") (pin "1") (pinfunction "1_1") (pintype "passive"))
    )
    (net (code "21") (name "/OUT16") (class "Default")
      (node (ref "P7") (pin "2") (pinfunction "2_2") (pintype "passive"))
      (node (ref "U4") (pin "2") (pinfunction "K_2") (pintype "passive"))
    )
    (net (code "22") (name "/P2_GND1") (class "Default")
      (node (ref "P8") (pin "2") (pinfunction "2_2") (pintype "passive"))
      (node (ref "RELAY2") (pin "4") (pinfunction "NO_4") (pintype "passive"))
    )
    (net (code "23") (name "/P2_GND2") (class "Default")
      (node (ref "P8") (pin "1") (pinfunction "1_1") (pintype "passive"))
      (node (ref "RELAY2") (pin "3") (pinfunction "C_3") (pintype "passive"))
    )
    (net (code "24") (name "/R+(RED)") (class "Default")
      (node (ref "P6") (pin "1") (pinfunction "1_1") (pintype "passive"))
      (node (ref "R39") (pin "1") (pinfunction "1_1") (pintype "passive"))
    )
    (net (code "25") (name "/R-(BLACK1)") (class "Default")
      (node (ref "P6") (pin "3") (pinfunction "3_3") (pintype "passive"))
      (node (ref "RELAY5") (pin "3") (pinfunction "C_3") (pintype "passive"))
      (node (ref "RELAY7") (pin "8") (pinfunction "C1_8") (pintype "passive"))
    )
    (net (code "26") (name "/R-(BLACK2)") (class "Default")
      (node (ref "P6") (pin "2") (pinfunction "2_2") (pintype "passive"))
      (node (ref "RELAY5") (pin "8") (pinfunction "C1_8") (pintype "passive"))
    )
    (net (code "27") (name "/RM3545_H1") (class "Default")
      (node (ref "P2") (pin "2") (pinfunction "2_2") (pintype "passive"))
      (node (ref "RELAY4") (pin "4") (pinfunction "NO_4") (pintype "passive"))
      (node (ref "RELAY5") (pin "4") (pinfunction "NO_4") (pintype "passive"))
    )
    (net (code "28") (name "/RM3545_H2") (class "Default")
      (node (ref "P2") (pin "1") (pinfunction "1_1") (pintype "passive"))
      (node (ref "RELAY4") (pin "7") (pinfunction "NO1_7") (pintype "passive"))
      (node (ref "RELAY5") (pin "7") (pinfunction "NO1_7") (pintype "passive"))
    )
    (net (code "29") (name "/USB_SHIELD") (class "Default")
      (node (ref "C1") (pin "2") (pinfunction "2_2") (pintype "passive"))
      (node (ref "R8") (pin "2") (pinfunction "2_2") (pintype "passive"))
      (node (ref "SB1") (pin "1") (pinfunction "1_1") (pintype "passive"))
      (node (ref "U2") (pin "5") (pinfunction "NC_5") (pintype "passive"))
      (node (ref "U2") (pin "6") (pinfunction "NC_6") (pintype "passive"))
    )
    (net (code "30") (name "/VCharge") (class "Default")
      (node (ref "R54") (pin "1") (pinfunction "1_1") (pintype "passive"))
      (node (ref "R55") (pin "2") (pinfunction "2_2") (pintype "passive"))
      (node (ref "RELAY1") (pin "2") (pinfunction "NC_2") (pintype "passive"))
      (node (ref "RELAY1") (pin "9") (pinfunction "NC1_9") (pintype "passive"))
    )
    (net (code "31") (name "24VDC") (class "Default")
      (node (ref "D1") (pin "1") (pinfunction "A_1") (pintype "passive"))
      (node (ref "P4") (pin "1") (pinfunction "1_1") (pintype "passive"))
    )
    (net (code "32") (name "GND") (class "Default")
      (node (ref "C1") (pin "1") (pinfunction "1_1") (pintype "passive"))
      (node (ref "C2") (pin "1") (pinfunction "1_1") (pintype "passive"))
      (node (ref "C3") (pin "2") (pinfunction "2_2") (pintype "passive"))
      (node (ref "C4") (pin "2") (pinfunction "2_2") (pintype "passive"))
      (node (ref "C7") (pin "2") (pinfunction "2_2") (pintype "passive"))
      (node (ref "D10") (pin "K") (pinfunction "K_K") (pintype "passive"))
      (node (ref "D11") (pin "1") (pinfunction "A_1") (pintype "passive"))
      (node (ref "D12") (pin "K") (pinfunction "K_K") (pintype "passive"))
      (node (ref "D13") (pin "1") (pinfunction "A_1") (pintype "passive"))
      (node (ref "D14") (pin "K") (pinfunction "K_K") (pintype "passive"))
      (node (ref "D15") (pin "1") (pinfunction "A_1") (pintype "passive"))
      (node (ref "D16") (pin "K") (pinfunction "K_K") (pintype "passive"))
      (node (ref "D17") (pin "1") (pinfunction "A_1") (pintype "passive"))
      (node (ref "D2") (pin "1") (pinfunction "A_1") (pintype "passive"))
      (node (ref "D3") (pin "K") (pinfunction "K_K") (pintype "passive"))
      (node (ref "D4") (pin "K") (pinfunction "K_K") (pintype "passive"))
      (node (ref "D5") (pin "1") (pinfunction "A_1") (pintype "passive"))
      (node (ref "D6") (pin "K") (pinfunction "K_K") (pintype "passive"))
      (node (ref "D7") (pin "1") (pinfunction "A_1") (pintype "passive"))
      (node (ref "D8") (pin "K") (pinfunction "K_K") (pintype "passive"))
      (node (ref "D9") (pin "1") (pinfunction "A_1") (pintype "passive"))
      (node (ref "P4") (pin "2") (pinfunction "2_2") (pintype "passive"))
      (node (ref "R1") (pin "1") (pinfunction "1_1") (pintype "passive"))
      (node (ref "R41") (pin "2") (pinfunction "2_2") (pintype "passive"))
      (node (ref "R44") (pin "1") (pinfunction "1_1") (pintype "passive"))
      (node (ref "R45") (pin "1") (pinfunction "1_1") (pintype "passive"))
      (node (ref "R49") (pin "1") (pinfunction "1_1") (pintype "passive"))
      (node (ref "R8") (pin "1") (pinfunction "1_1") (pintype "passive"))
      (node (ref "RELAY1") (pin "10") (pinfunction "-_10") (pintype "passive"))
      (node (ref "RELAY2") (pin "10") (pinfunction "-_10") (pintype "passive"))
      (node (ref "RELAY2") (pin "7") (pinfunction "NO1_7") (pintype "passive"))
      (node (ref "RELAY3") (pin "10") (pinfunction "-_10") (pintype "passive"))
      (node (ref "RELAY4") (pin "10") (pinfunction "-_10") (pintype "passive"))
      (node (ref "RELAY5") (pin "10") (pinfunction "-_10") (pintype "passive"))
      (node (ref "RELAY6") (pin "10") (pinfunction "-_10") (pintype "passive"))
      (node (ref "RELAY7") (pin "10") (pinfunction "-_10") (pintype "passive"))
      (node (ref "SB1") (pin "2") (pinfunction "2_2") (pintype "passive"))
      (node (ref "U1") (pin "3") (pinfunction "GND_3") (pintype "passive"))
      (node (ref "U3") (pin "3") (pinfunction "E_3") (pintype "passive"))
      (node (ref "U4") (pin "3") (pinfunction "E_3") (pintype "passive"))
      (node (ref "U5") (pin "3") (pinfunction "E_3") (pintype "passive"))
      (node (ref "U6") (pin "3") (pinfunction "E_3") (pintype "passive"))
      (node (ref "U7") (pin "3") (pinfunction "E_3") (pintype "passive"))
      (node (ref "U8") (pin "3") (pinfunction "E_3") (pintype "passive"))
      (node (ref "U9") (pin "3") (pinfunction "E_3") (pintype "passive"))
    )
    (net (code "33") (name "Net-(D2-K)") (class "Default")
      (node (ref "D2") (pin "2") (pinfunction "K_2") (pintype "passive"))
      (node (ref "L1") (pin "1") (pinfunction "1_1") (pintype "passive"))
      (node (ref "U1") (pin "2") (pinfunction "V_out_2") (pintype "passive"))
    )
    (net (code "34") (name "Net-(D3-PadA)") (class "Default")
      (node (ref "D3") (pin "A") (pinfunction "A_A") (pintype "passive"))
      (node (ref "R3") (pin "1") (pinfunction "1_1") (pintype "passive"))
    )
    (net (code "35") (name "Net-(D4-PadA)") (class "Default")
      (node (ref "D4") (pin "A") (pinfunction "A_A") (pintype "passive"))
      (node (ref "R12") (pin "2") (pinfunction "2_2") (pintype "passive"))
    )
    (net (code "36") (name "Net-(D5-K)") (class "Default")
      (node (ref "D5") (pin "2") (pinfunction "K_2") (pintype "passive"))
      (node (ref "Q1") (pin "3") (pinfunction "C_3") (pintype "passive"))
      (node (ref "R12") (pin "1") (pinfunction "1_1") (pintype "passive"))
      (node (ref "RELAY1") (pin "1") (pinfunction "+_1") (pintype "passive"))
    )
    (net (code "37") (name "Net-(D6-PadA)") (class "Default")
      (node (ref "D6") (pin "A") (pinfunction "A_A") (pintype "passive"))
      (node (ref "R16") (pin "2") (pinfunction "2_2") (pintype "passive"))
    )
    (net (code "38") (name "Net-(D7-K)") (class "Default")
      (node (ref "D7") (pin "2") (pinfunction "K_2") (pintype "passive"))
      (node (ref "Q2") (pin "3") (pinfunction "C_3") (pintype "passive"))
      (node (ref "R16") (pin "1") (pinfunction "1_1") (pintype "passive"))
      (node (ref "RELAY2") (pin "1") (pinfunction "+_1") (pintype "passive"))
    )
    (net (code "39") (name "Net-(D8-PadA)") (class "Default")
      (node (ref "D8") (pin "A") (pinfunction "A_A") (pintype "passive"))
      (node (ref "R20") (pin "2") (pinfunction "2_2") (pintype "passive"))
    )
    (net (code "40") (name "Net-(D9-K)") (class "Default")
      (node (ref "D9") (pin "2") (pinfunction "K_2") (pintype "passive"))
      (node (ref "Q3") (pin "3") (pinfunction "C_3") (pintype "passive"))
      (node (ref "R20") (pin "1") (pinfunction "1_1") (pintype "passive"))
      (node (ref "RELAY3") (pin "1") (pinfunction "+_1") (pintype "passive"))
    )
    (net (code "41") (name "Net-(D10-PadA)") (class "Default")
      (node (ref "D10") (pin "A") (pinfunction "A_A") (pintype "passive"))
      (node (ref "R24") (pin "2") (pinfunction "2_2") (pintype "passive"))
    )
    (net (code "42") (name "Net-(D11-K)") (class "Default")
      (node (ref "D11") (pin "2") (pinfunction "K_2") (pintype "passive"))
      (node (ref "Q4") (pin "3") (pinfunction "C_3") (pintype "passive"))
      (node (ref "R24") (pin "1") (pinfunction "1_1") (pintype "passive"))
      (node (ref "RELAY4") (pin "1") (pinfunction "+_1") (pintype "passive"))
    )
    (net (code "43") (name "Net-(D12-PadA)") (class "Default")
      (node (ref "D12") (pin "A") (pinfunction "A_A") (pintype "passive"))
      (node (ref "R28") (pin "2") (pinfunction "2_2") (pintype "passive"))
    )
    (net (code "44") (name "Net-(D13-K)") (class "Default")
      (node (ref "D13") (pin "2") (pinfunction "K_2") (pintype "passive"))
      (node (ref "Q5") (pin "3") (pinfunction "C_3") (pintype "passive"))
      (node (ref "R28") (pin "1") (pinfunction "1_1") (pintype "passive"))
      (node (ref "RELAY5") (pin "1") (pinfunction "+_1") (pintype "passive"))
    )
    (net (code "45") (name "Net-(D14-PadA)") (class "Default")
      (node (ref "D14") (pin "A") (pinfunction "A_A") (pintype "passive"))
      (node (ref "R32") (pin "2") (pinfunction "2_2") (pintype "passive"))
    )
    (net (code "46") (name "Net-(D15-K)") (class "Default")
      (node (ref "D15") (pin "2") (pinfunction "K_2") (pintype "passive"))
      (node (ref "Q6") (pin "3") (pinfunction "C_3") (pintype "passive"))
      (node (ref "R32") (pin "1") (pinfunction "1_1") (pintype "passive"))
      (node (ref "RELAY6") (pin "1") (pinfunction "+_1") (pintype "passive"))
    )
    (net (code "47") (name "Net-(D16-PadA)") (class "Default")
      (node (ref "D16") (pin "A") (pinfunction "A_A") (pintype "passive"))
      (node (ref "R38") (pin "2") (pinfunction "2_2") (pintype "passive"))
    )
    (net (code "48") (name "Net-(D17-K)") (class "Default")
      (node (ref "D17") (pin "2") (pinfunction "K_2") (pintype "passive"))
      (node (ref "Q7") (pin "3") (pinfunction "C_3") (pintype "passive"))
      (node (ref "R38") (pin "1") (pinfunction "1_1") (pintype "passive"))
      (node (ref "RELAY7") (pin "1") (pinfunction "+_1") (pintype "passive"))
    )
    (net (code "49") (name "Net-(Q1-B)") (class "Default")
      (node (ref "Q1") (pin "1") (pinfunction "B_1") (pintype "passive"))
      (node (ref "R11") (pin "2") (pinfunction "2_2") (pintype "passive"))
    )
    (net (code "50") (name "Net-(Q2-B)") (class "Default")
      (node (ref "Q2") (pin "1") (pinfunction "B_1") (pintype "passive"))
      (node (ref "R15") (pin "2") (pinfunction "2_2") (pintype "passive"))
    )
    (net (code "51") (name "Net-(Q3-B)") (class "Default")
      (node (ref "Q3") (pin "1") (pinfunction "B_1") (pintype "passive"))
      (node (ref "R19") (pin "2") (pinfunction "2_2") (pintype "passive"))
    )
    (net (code "52") (name "Net-(Q4-B)") (class "Default")
      (node (ref "Q4") (pin "1") (pinfunction "B_1") (pintype "passive"))
      (node (ref "R23") (pin "2") (pinfunction "2_2") (pintype "passive"))
    )
    (net (code "53") (name "Net-(Q5-B)") (class "Default")
      (node (ref "Q5") (pin "1") (pinfunction "B_1") (pintype "passive"))
      (node (ref "R27") (pin "2") (pinfunction "2_2") (pintype "passive"))
    )
    (net (code "54") (name "Net-(Q6-B)") (class "Default")
      (node (ref "Q6") (pin "1") (pinfunction "B_1") (pintype "passive"))
      (node (ref "R31") (pin "2") (pinfunction "2_2") (pintype "passive"))
    )
    (net (code "55") (name "Net-(Q7-B)") (class "Default")
      (node (ref "Q7") (pin "1") (pinfunction "B_1") (pintype "passive"))
      (node (ref "R37") (pin "2") (pinfunction "2_2") (pintype "passive"))
    )
    (net (code "56") (name "Net-(R33-Pad2)") (class "Default")
      (node (ref "R33") (pin "2") (pinfunction "2_2") (pintype "passive"))
      (node (ref "R34") (pin "2") (pinfunction "2_2") (pintype "passive"))
    )
    (net (code "57") (name "Net-(R39-Pad2)") (class "Default")
      (node (ref "R39") (pin "2") (pinfunction "2_2") (pintype "passive"))
      (node (ref "R40") (pin "2") (pinfunction "2_2") (pintype "passive"))
    )
    (net (code "58") (name "Net-(R43-Pad2)") (class "Default")
      (node (ref "R43") (pin "2") (pinfunction "2_2") (pintype "passive"))
      (node (ref "R54") (pin "2") (pinfunction "2_2") (pintype "passive"))
      (node (ref "R55") (pin "1") (pinfunction "1_1") (pintype "passive"))
    )
    (net (code "59") (name "Net-(R46-BOT)") (class "Default")
      (node (ref "R46") (pin "2") (pinfunction "BOT_2") (pintype "passive"))
      (node (ref "R46") (pin "3") (pinfunction "TAP_3") (pintype "passive"))
      (node (ref "R52") (pin "2") (pinfunction "2_2") (pintype "passive"))
    )
    (net (code "60") (name "Net-(R46-TOP)") (class "Default")
      (node (ref "R46") (pin "1") (pinfunction "TOP_1") (pintype "passive"))
      (node (ref "R53") (pin "1") (pinfunction "1_1") (pintype "passive"))
    )
    (net (code "61") (name "Net-(R47-BOT)") (class "Default")
      (node (ref "R2") (pin "2") (pinfunction "2_2") (pintype "passive"))
      (node (ref "R47") (pin "2") (pinfunction "BOT_2") (pintype "passive"))
      (node (ref "R47") (pin "3") (pinfunction "TAP_3") (pintype "passive"))
      (node (ref "R56") (pin "1") (pinfunction "1_1") (pintype "passive"))
      (node (ref "R57") (pin "2") (pinfunction "2_2") (pintype "passive"))
    )
    (net (code "62") (name "Net-(R48-Pad1)") (class "Default")
      (node (ref "R48") (pin "1") (pinfunction "1_1") (pintype "passive"))
      (node (ref "R50") (pin "2") (pinfunction "2_2") (pintype "passive"))
      (node (ref "R51") (pin "1") (pinfunction "1_1") (pintype "passive"))
    )
    (net (code "63") (name "Net-(RELAY3-NO)") (class "Default")
      (node (ref "R42") (pin "2") (pinfunction "2_2") (pintype "passive"))
      (node (ref "RELAY3") (pin "4") (pinfunction "NO_4") (pintype "passive"))
    )
    (net (code "64") (name "Net-(RELAY6-C)") (class "Default")
      (node (ref "R34") (pin "1") (pinfunction "1_1") (pintype "passive"))
      (node (ref "RELAY6") (pin "3") (pinfunction "C_3") (pintype "passive"))
    )
    (net (code "65") (name "Net-(RELAY7-C)") (class "Default")
      (node (ref "R40") (pin "1") (pinfunction "1_1") (pintype "passive"))
      (node (ref "RELAY7") (pin "3") (pinfunction "C_3") (pintype "passive"))
    )
    (net (code "66") (name "Net-(U1-FB)") (class "Default")
      (node (ref "R1") (pin "2") (pinfunction "2_2") (pintype "passive"))
      (node (ref "R2") (pin "1") (pinfunction "1_1") (pintype "passive"))
      (node (ref "R45") (pin "2") (pinfunction "2_2") (pintype "passive"))
      (node (ref "R57") (pin "1") (pinfunction "1_1") (pintype "passive"))
      (node (ref "U1") (pin "4") (pinfunction "FB_4") (pintype "passive"))
    )
    (net (code "67") (name "Net-(U3-A)") (class "Default")
      (node (ref "R9") (pin "1") (pinfunction "1_1") (pintype "passive"))
      (node (ref "U3") (pin "1") (pinfunction "A_1") (pintype "passive"))
    )
    (net (code "68") (name "Net-(U3-C)") (class "Default")
      (node (ref "R10") (pin "1") (pinfunction "1_1") (pintype "passive"))
      (node (ref "R11") (pin "1") (pinfunction "1_1") (pintype "passive"))
      (node (ref "U3") (pin "4") (pinfunction "C_4") (pintype "passive"))
    )
    (net (code "69") (name "Net-(U4-A)") (class "Default")
      (node (ref "R13") (pin "1") (pinfunction "1_1") (pintype "passive"))
      (node (ref "U4") (pin "1") (pinfunction "A_1") (pintype "passive"))
    )
    (net (code "70") (name "Net-(U4-C)") (class "Default")
      (node (ref "R14") (pin "1") (pinfunction "1_1") (pintype "passive"))
      (node (ref "R15") (pin "1") (pinfunction "1_1") (pintype "passive"))
      (node (ref "U4") (pin "4") (pinfunction "C_4") (pintype "passive"))
    )
    (net (code "71") (name "Net-(U5-A)") (class "Default")
      (node (ref "R17") (pin "1") (pinfunction "1_1") (pintype "passive"))
      (node (ref "U5") (pin "1") (pinfunction "A_1") (pintype "passive"))
    )
    (net (code "72") (name "Net-(U5-C)") (class "Default")
      (node (ref "R18") (pin "1") (pinfunction "1_1") (pintype "passive"))
      (node (ref "R19") (pin "1") (pinfunction "1_1") (pintype "passive"))
      (node (ref "U5") (pin "4") (pinfunction "C_4") (pintype "passive"))
    )
    (net (code "73") (name "Net-(U6-A)") (class "Default")
      (node (ref "R21") (pin "1") (pinfunction "1_1") (pintype "passive"))
      (node (ref "U6") (pin "1") (pinfunction "A_1") (pintype "passive"))
    )
    (net (code "74") (name "Net-(U6-C)") (class "Default")
      (node (ref "R22") (pin "1") (pinfunction "1_1") (pintype "passive"))
      (node (ref "R23") (pin "1") (pinfunction "1_1") (pintype "passive"))
      (node (ref "U6") (pin "4") (pinfunction "C_4") (pintype "passive"))
    )
    (net (code "75") (name "Net-(U7-A)") (class "Default")
      (node (ref "R25") (pin "1") (pinfunction "1_1") (pintype "passive"))
      (node (ref "U7") (pin "1") (pinfunction "A_1") (pintype "passive"))
    )
    (net (code "76") (name "Net-(U7-C)") (class "Default")
      (node (ref "R26") (pin "1") (pinfunction "1_1") (pintype "passive"))
      (node (ref "R27") (pin "1") (pinfunction "1_1") (pintype "passive"))
      (node (ref "U7") (pin "4") (pinfunction "C_4") (pintype "passive"))
    )
    (net (code "77") (name "Net-(U8-A)") (class "Default")
      (node (ref "R29") (pin "1") (pinfunction "1_1") (pintype "passive"))
      (node (ref "U8") (pin "1") (pinfunction "A_1") (pintype "passive"))
    )
    (net (code "78") (name "Net-(U8-C)") (class "Default")
      (node (ref "R30") (pin "1") (pinfunction "1_1") (pintype "passive"))
      (node (ref "R31") (pin "1") (pinfunction "1_1") (pintype "passive"))
      (node (ref "U8") (pin "4") (pinfunction "C_4") (pintype "passive"))
    )
    (net (code "79") (name "Net-(U9-A)") (class "Default")
      (node (ref "R35") (pin "1") (pinfunction "1_1") (pintype "passive"))
      (node (ref "U9") (pin "1") (pinfunction "A_1") (pintype "passive"))
    )
    (net (code "80") (name "Net-(U9-C)") (class "Default")
      (node (ref "R36") (pin "1") (pinfunction "1_1") (pintype "passive"))
      (node (ref "R37") (pin "1") (pinfunction "1_1") (pintype "passive"))
      (node (ref "U9") (pin "4") (pinfunction "C_4") (pintype "passive"))
    )
    (net (code "81") (name "unconnected-(RELAY1-NO-Pad4)") (class "Default")
      (node (ref "RELAY1") (pin "4") (pinfunction "NO_4") (pintype "passive"))
    )
    (net (code "82") (name "unconnected-(RELAY1-NO1-Pad7)") (class "Default")
      (node (ref "RELAY1") (pin "7") (pinfunction "NO1_7") (pintype "passive"))
    )
    (net (code "83") (name "unconnected-(RELAY1-Pad5)") (class "Default")
      (node (ref "RELAY1") (pin "5") (pinfunction "5_5") (pintype "passive"))
    )
    (net (code "84") (name "unconnected-(RELAY1-Pad6)") (class "Default")
      (node (ref "RELAY1") (pin "6") (pinfunction "6_6") (pintype "passive"))
    )
    (net (code "85") (name "unconnected-(RELAY2-NC-Pad2)") (class "Default")
      (node (ref "RELAY2") (pin "2") (pinfunction "NC_2") (pintype "passive"))
    )
    (net (code "86") (name "unconnected-(RELAY2-NC1-Pad9)") (class "Default")
      (node (ref "RELAY2") (pin "9") (pinfunction "NC1_9") (pintype "passive"))
    )
    (net (code "87") (name "unconnected-(RELAY2-Pad5)") (class "Default")
      (node (ref "RELAY2") (pin "5") (pinfunction "5_5") (pintype "passive"))
    )
    (net (code "88") (name "unconnected-(RELAY2-Pad6)") (class "Default")
      (node (ref "RELAY2") (pin "6") (pinfunction "6_6") (pintype "passive"))
    )
    (net (code "89") (name "unconnected-(RELAY3-NC-Pad2)") (class "Default")
      (node (ref "RELAY3") (pin "2") (pinfunction "NC_2") (pintype "passive"))
    )
    (net (code "90") (name "unconnected-(RELAY3-NC1-Pad9)") (class "Default")
      (node (ref "RELAY3") (pin "9") (pinfunction "NC1_9") (pintype "passive"))
    )
    (net (code "91") (name "unconnected-(RELAY3-Pad5)") (class "Default")
      (node (ref "RELAY3") (pin "5") (pinfunction "5_5") (pintype "passive"))
    )
    (net (code "92") (name "unconnected-(RELAY3-Pad6)") (class "Default")
      (node (ref "RELAY3") (pin "6") (pinfunction "6_6") (pintype "passive"))
    )
    (net (code "93") (name "unconnected-(RELAY4-NC-Pad2)") (class "Default")
      (node (ref "RELAY4") (pin "2") (pinfunction "NC_2") (pintype "passive"))
    )
    (net (code "94") (name "unconnected-(RELAY4-NC1-Pad9)") (class "Default")
      (node (ref "RELAY4") (pin "9") (pinfunction "NC1_9") (pintype "passive"))
    )
    (net (code "95") (name "unconnected-(RELAY4-Pad5)") (class "Default")
      (node (ref "RELAY4") (pin "5") (pinfunction "5_5") (pintype "passive"))
    )
    (net (code "96") (name "unconnected-(RELAY4-Pad6)") (class "Default")
      (node (ref "RELAY4") (pin "6") (pinfunction "6_6") (pintype "passive"))
    )
    (net (code "97") (name "unconnected-(RELAY5-NC-Pad2)") (class "Default")
      (node (ref "RELAY5") (pin "2") (pinfunction "NC_2") (pintype "passive"))
    )
    (net (code "98") (name "unconnected-(RELAY5-NC1-Pad9)") (class "Default")
      (node (ref "RELAY5") (pin "9") (pinfunction "NC1_9") (pintype "passive"))
    )
    (net (code "99") (name "unconnected-(RELAY5-Pad5)") (class "Default")
      (node (ref "RELAY5") (pin "5") (pinfunction "5_5") (pintype "passive"))
    )
    (net (code "100") (name "unconnected-(RELAY5-Pad6)") (class "Default")
      (node (ref "RELAY5") (pin "6") (pinfunction "6_6") (pintype "passive"))
    )
    (net (code "101") (name "unconnected-(RELAY6-NC-Pad2)") (class "Default")
      (node (ref "RELAY6") (pin "2") (pinfunction "NC_2") (pintype "passive"))
    )
    (net (code "102") (name "unconnected-(RELAY6-NC1-Pad9)") (class "Default")
      (node (ref "RELAY6") (pin "9") (pinfunction "NC1_9") (pintype "passive"))
    )
    (net (code "103") (name "unconnected-(RELAY6-Pad5)") (class "Default")
      (node (ref "RELAY6") (pin "5") (pinfunction "5_5") (pintype "passive"))
    )
    (net (code "104") (name "unconnected-(RELAY6-Pad6)") (class "Default")
      (node (ref "RELAY6") (pin "6") (pinfunction "6_6") (pintype "passive"))
    )
    (net (code "105") (name "unconnected-(RELAY7-NC-Pad2)") (class "Default")
      (node (ref "RELAY7") (pin "2") (pinfunction "NC_2") (pintype "passive"))
    )
    (net (code "106") (name "unconnected-(RELAY7-NC1-Pad9)") (class "Default")
      (node (ref "RELAY7") (pin "9") (pinfunction "NC1_9") (pintype "passive"))
    )
    (net (code "107") (name "unconnected-(RELAY7-Pad5)") (class "Default")
      (node (ref "RELAY7") (pin "5") (pinfunction "5_5") (pintype "passive"))
    )
    (net (code "108") (name "unconnected-(RELAY7-Pad6)") (class "Default")
      (node (ref "RELAY7") (pin "6") (pinfunction "6_6") (pintype "passive"))
    )
  )
)
